# ProgrammableOLED.net
KiCad netlist of a schematic drawn in EAGLE
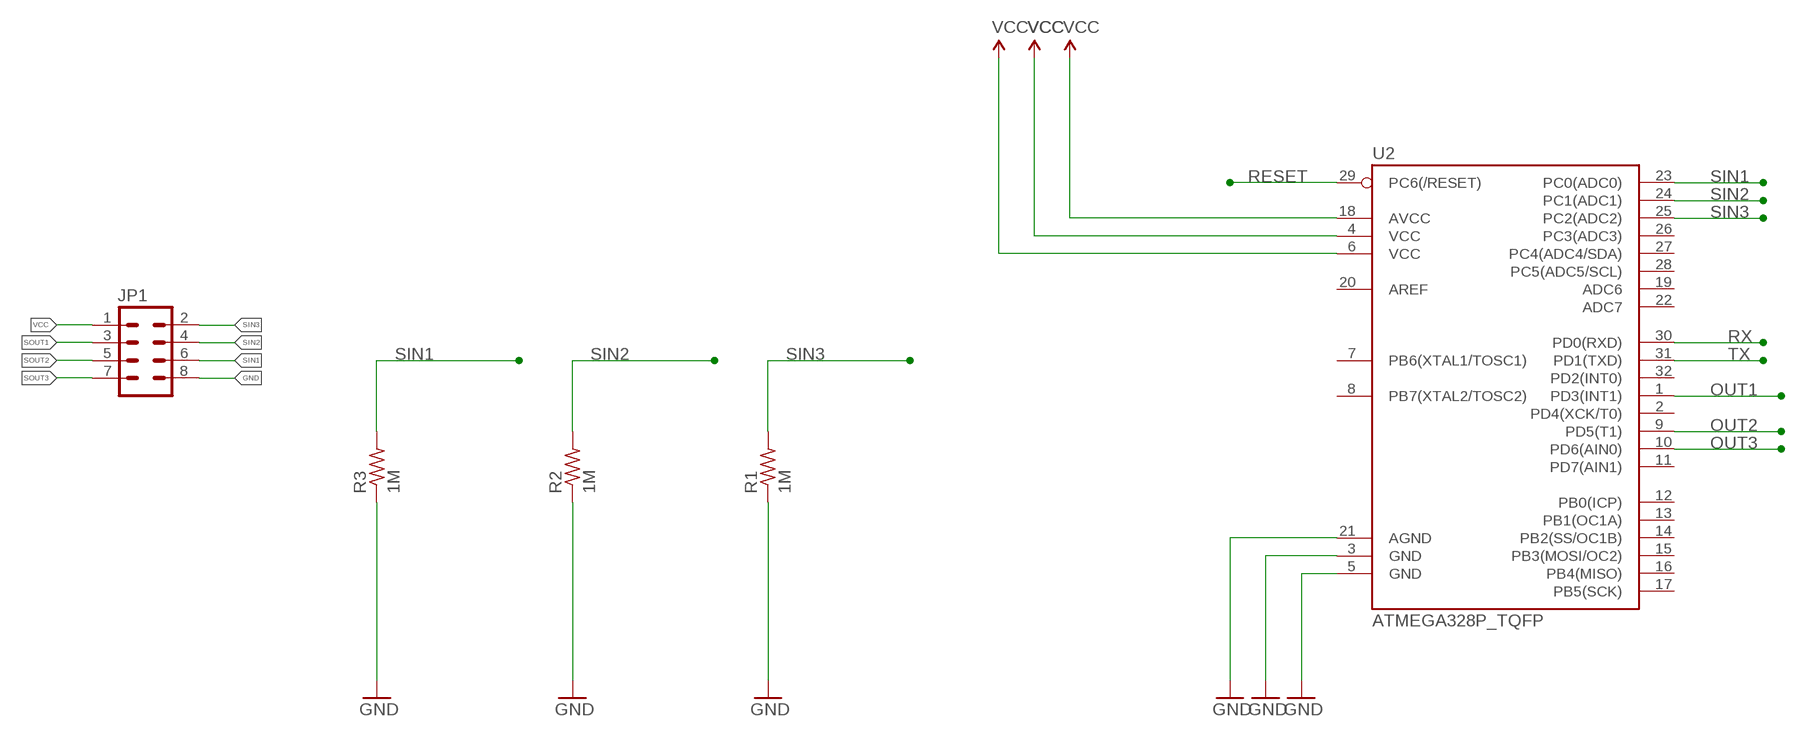
[diagram p0: schematic, sheet 1, part 1 of 2]
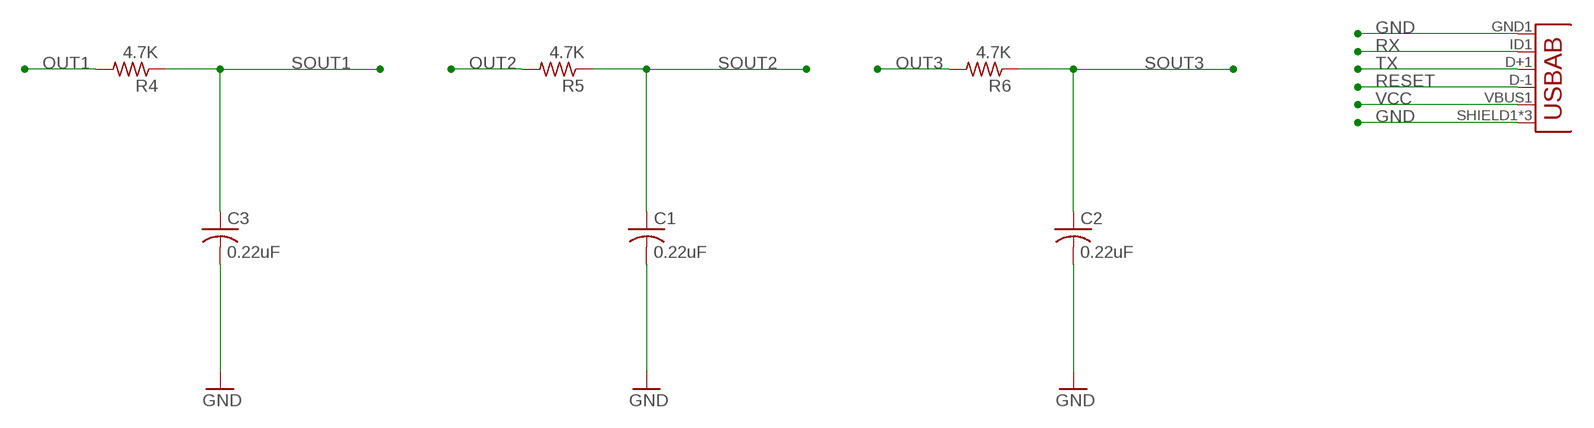
[diagram p1: schematic, sheet 1, part 2 of 2]

(export (version "E")
  (design (tool "Eeschema 10.0.6"))
  (components
    (comp (ref "C1")
      (value "0.22uF")
      (footprint "eagle-import:C0603")
      (libsource (lib "eagle-import") (part "C-USC0603"))
    )
    (comp (ref "C2")
      (value "0.22uF")
      (footprint "eagle-import:C0603")
      (libsource (lib "eagle-import") (part "C-USC0603"))
    )
    (comp (ref "C3")
      (value "0.22uF")
      (footprint "eagle-import:C0603")
      (libsource (lib "eagle-import") (part "C-USC0603"))
    )
    (comp (ref "JP1")
      (value "M04X2")
      (footprint "eagle-import:2X4")
      (libsource (lib "eagle-import") (part "M04X2"))
    )
    (comp (ref "JP5")
      (value "USB-ABCONN-11794")
      (footprint "eagle-import:USB-AB-MICRO-SMD_V03")
      (libsource (lib "eagle-import") (part "USB-ABCONN-11794"))
    )
    (comp (ref "R1")
      (value "1M")
      (footprint "eagle-import:R0603")
      (libsource (lib "eagle-import") (part "R-US_R0603"))
    )
    (comp (ref "R2")
      (value "1M")
      (footprint "eagle-import:R0603")
      (libsource (lib "eagle-import") (part "R-US_R0603"))
    )
    (comp (ref "R3")
      (value "1M")
      (footprint "eagle-import:R0603")
      (libsource (lib "eagle-import") (part "R-US_R0603"))
    )
    (comp (ref "R4")
      (value "4.7K")
      (footprint "eagle-import:R0603")
      (libsource (lib "eagle-import") (part "R-US_R0603"))
    )
    (comp (ref "R5")
      (value "4.7K")
      (footprint "eagle-import:R0603")
      (libsource (lib "eagle-import") (part "R-US_R0603"))
    )
    (comp (ref "R6")
      (value "4.7K")
      (footprint "eagle-import:R0603")
      (libsource (lib "eagle-import") (part "R-US_R0603"))
    )
    (comp (ref "U2")
      (value "ATMEGA328P_TQFP")
      (footprint "eagle-import:TQFP32-08")
      (libsource (lib "eagle-import") (part "ATMEGA328P_TQFP"))
    )
  )
  (nets
    (net (code "1") (name "/OUT1") (class "Default")
      (node (ref "R4") (pin "2") (pinfunction "2_2") (pintype "passive"))
      (node (ref "U2") (pin "1") (pinfunction "PD3(INT1)_1") (pintype "bidirectional"))
    )
    (net (code "2") (name "/OUT2") (class "Default")
      (node (ref "R5") (pin "2") (pinfunction "2_2") (pintype "passive"))
      (node (ref "U2") (pin "9") (pinfunction "PD5(T1)_9") (pintype "bidirectional"))
    )
    (net (code "3") (name "/OUT3") (class "Default")
      (node (ref "R6") (pin "2") (pinfunction "2_2") (pintype "passive"))
      (node (ref "U2") (pin "10") (pinfunction "PD6(AIN0)_10") (pintype "bidirectional"))
    )
    (net (code "4") (name "/RESET") (class "Default")
      (node (ref "JP5") (pin "D-1") (pinfunction "D-_D-1") (pintype "bidirectional"))
      (node (ref "U2") (pin "29") (pinfunction "PC6(/RESET)_29") (pintype "bidirectional"))
    )
    (net (code "5") (name "/RX") (class "Default")
      (node (ref "JP5") (pin "ID1") (pinfunction "USBID_ID1") (pintype "bidirectional"))
      (node (ref "U2") (pin "30") (pinfunction "PD0(RXD)_30") (pintype "bidirectional"))
    )
    (net (code "6") (name "/TX") (class "Default")
      (node (ref "JP5") (pin "D+1") (pinfunction "D+_D+1") (pintype "bidirectional"))
      (node (ref "U2") (pin "31") (pinfunction "PD1(TXD)_31") (pintype "bidirectional"))
    )
    (net (code "7") (name "GND") (class "Default")
      (node (ref "C1") (pin "2") (pinfunction "2_2") (pintype "passive"))
      (node (ref "C2") (pin "2") (pinfunction "2_2") (pintype "passive"))
      (node (ref "C3") (pin "2") (pinfunction "2_2") (pintype "passive"))
      (node (ref "JP1") (pin "8") (pinfunction "8_8") (pintype "passive"))
      (node (ref "JP5") (pin "GND1") (pinfunction "GND_GND1") (pintype "bidirectional"))
      (node (ref "JP5") (pin "SHIELD1") (pinfunction "SHIELD_SHIELD1") (pintype "bidirectional"))
      (node (ref "JP5") (pin "SHIELD2") (pinfunction "SHIELD_SHIELD2") (pintype "bidirectional"))
      (node (ref "JP5") (pin "SHIELD3") (pinfunction "SHIELD_SHIELD3") (pintype "bidirectional"))
      (node (ref "R1") (pin "1") (pinfunction "1_1") (pintype "passive"))
      (node (ref "R2") (pin "1") (pinfunction "1_1") (pintype "passive"))
      (node (ref "R3") (pin "1") (pinfunction "1_1") (pintype "passive"))
      (node (ref "U2") (pin "21") (pinfunction "AGND_21") (pintype "bidirectional"))
      (node (ref "U2") (pin "3") (pinfunction "GND_3") (pintype "bidirectional"))
      (node (ref "U2") (pin "5") (pinfunction "GND_5") (pintype "bidirectional"))
    )
    (net (code "8") (name "SIN1") (class "Default")
      (node (ref "JP1") (pin "6") (pinfunction "6_6") (pintype "passive"))
      (node (ref "R3") (pin "2") (pinfunction "2_2") (pintype "passive"))
      (node (ref "U2") (pin "23") (pinfunction "PC0(ADC0)_23") (pintype "bidirectional"))
    )
    (net (code "9") (name "SIN2") (class "Default")
      (node (ref "JP1") (pin "4") (pinfunction "4_4") (pintype "passive"))
      (node (ref "R2") (pin "2") (pinfunction "2_2") (pintype "passive"))
      (node (ref "U2") (pin "24") (pinfunction "PC1(ADC1)_24") (pintype "bidirectional"))
    )
    (net (code "10") (name "SIN3") (class "Default")
      (node (ref "JP1") (pin "2") (pinfunction "2_2") (pintype "passive"))
      (node (ref "R1") (pin "2") (pinfunction "2_2") (pintype "passive"))
      (node (ref "U2") (pin "25") (pinfunction "PC2(ADC2)_25") (pintype "bidirectional"))
    )
    (net (code "11") (name "SOUT1") (class "Default")
      (node (ref "C3") (pin "1") (pinfunction "1_1") (pintype "passive"))
      (node (ref "JP1") (pin "3") (pinfunction "3_3") (pintype "passive"))
      (node (ref "R4") (pin "1") (pinfunction "1_1") (pintype "passive"))
    )
    (net (code "12") (name "SOUT2") (class "Default")
      (node (ref "C1") (pin "1") (pinfunction "1_1") (pintype "passive"))
      (node (ref "JP1") (pin "5") (pinfunction "5_5") (pintype "passive"))
      (node (ref "R5") (pin "1") (pinfunction "1_1") (pintype "passive"))
    )
    (net (code "13") (name "SOUT3") (class "Default")
      (node (ref "C2") (pin "1") (pinfunction "1_1") (pintype "passive"))
      (node (ref "JP1") (pin "7") (pinfunction "7_7") (pintype "passive"))
      (node (ref "R6") (pin "1") (pinfunction "1_1") (pintype "passive"))
    )
    (net (code "14") (name "VCC") (class "Default")
      (node (ref "JP1") (pin "1") (pinfunction "1_1") (pintype "passive"))
      (node (ref "JP5") (pin "VBUS1") (pinfunction "VBUS_VBUS1") (pintype "bidirectional"))
      (node (ref "U2") (pin "18") (pinfunction "AVCC_18") (pintype "bidirectional"))
      (node (ref "U2") (pin "4") (pinfunction "VCC_4") (pintype "bidirectional"))
      (node (ref "U2") (pin "6") (pinfunction "VCC_6") (pintype "bidirectional"))
    )
    (net (code "15") (name "unconnected-(U2-ADC6-Pad19)") (class "Default")
      (node (ref "U2") (pin "19") (pinfunction "ADC6_19") (pintype "bidirectional"))
    )
    (net (code "16") (name "unconnected-(U2-ADC7-Pad22)") (class "Default")
      (node (ref "U2") (pin "22") (pinfunction "ADC7_22") (pintype "bidirectional"))
    )
    (net (code "17") (name "unconnected-(U2-AREF-Pad20)") (class "Default")
      (node (ref "U2") (pin "20") (pinfunction "AREF_20") (pintype "bidirectional"))
    )
    (net (code "18") (name "unconnected-(U2-PB0(ICP)-Pad12)") (class "Default")
      (node (ref "U2") (pin "12") (pinfunction "PB0(ICP)_12") (pintype "bidirectional"))
    )
    (net (code "19") (name "unconnected-(U2-PB1(OC1A)-Pad13)") (class "Default")
      (node (ref "U2") (pin "13") (pinfunction "PB1(OC1A)_13") (pintype "bidirectional"))
    )
    (net (code "20") (name "unconnected-(U2-PB2(SS{slash}OC1B)-Pad14)") (class "Default")
      (node (ref "U2") (pin "14") (pinfunction "PB2(SS/OC1B)_14") (pintype "bidirectional"))
    )
    (net (code "21") (name "unconnected-(U2-PB3(MOSI{slash}OC2)-Pad15)") (class "Default")
      (node (ref "U2") (pin "15") (pinfunction "PB3(MOSI/OC2)_15") (pintype "bidirectional"))
    )
    (net (code "22") (name "unconnected-(U2-PB4(MISO)-Pad16)") (class "Default")
      (node (ref "U2") (pin "16") (pinfunction "PB4(MISO)_16") (pintype "bidirectional"))
    )
    (net (code "23") (name "unconnected-(U2-PB5(SCK)-Pad17)") (class "Default")
      (node (ref "U2") (pin "17") (pinfunction "PB5(SCK)_17") (pintype "bidirectional"))
    )
    (net (code "24") (name "unconnected-(U2-PB6(XTAL1{slash}TOSC1)-Pad7)") (class "Default")
      (node (ref "U2") (pin "7") (pinfunction "PB6(XTAL1/TOSC1)_7") (pintype "bidirectional"))
    )
    (net (code "25") (name "unconnected-(U2-PB7(XTAL2{slash}TOSC2)-Pad8)") (class "Default")
      (node (ref "U2") (pin "8") (pinfunction "PB7(XTAL2/TOSC2)_8") (pintype "bidirectional"))
    )
    (net (code "26") (name "unconnected-(U2-PC3(ADC3)-Pad26)") (class "Default")
      (node (ref "U2") (pin "26") (pinfunction "PC3(ADC3)_26") (pintype "bidirectional"))
    )
    (net (code "27") (name "unconnected-(U2-PC4(ADC4{slash}SDA)-Pad27)") (class "Default")
      (node (ref "U2") (pin "27") (pinfunction "PC4(ADC4/SDA)_27") (pintype "bidirectional"))
    )
    (net (code "28") (name "unconnected-(U2-PC5(ADC5{slash}SCL)-Pad28)") (class "Default")
      (node (ref "U2") (pin "28") (pinfunction "PC5(ADC5/SCL)_28") (pintype "bidirectional"))
    )
    (net (code "29") (name "unconnected-(U2-PD2(INT0)-Pad32)") (class "Default")
      (node (ref "U2") (pin "32") (pinfunction "PD2(INT0)_32") (pintype "bidirectional"))
    )
    (net (code "30") (name "unconnected-(U2-PD4(XCK{slash}T0)-Pad2)") (class "Default")
      (node (ref "U2") (pin "2") (pinfunction "PD4(XCK/T0)_2") (pintype "bidirectional"))
    )
    (net (code "31") (name "unconnected-(U2-PD7(AIN1)-Pad11)") (class "Default")
      (node (ref "U2") (pin "11") (pinfunction "PD7(AIN1)_11") (pintype "bidirectional"))
    )
  )
)
